# Emat.net
KiCad netlist of a schematic drawn in EAGLE
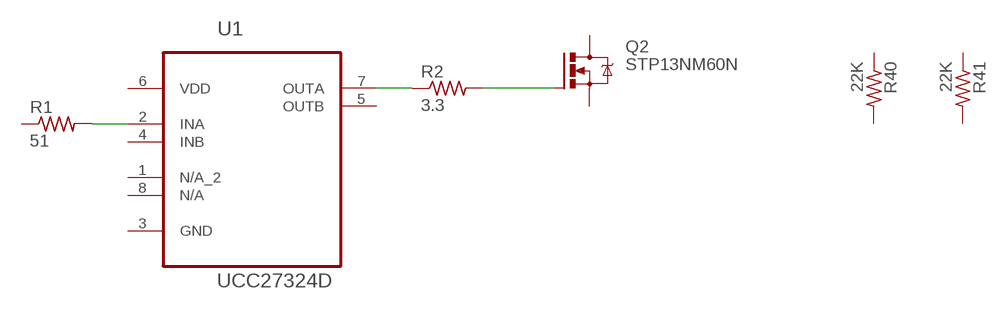
[diagram p0: schematic, sheet 1]

(export (version "E")
  (design (tool "Eeschema 10.0.6"))
  (components
    (comp (ref "Q2")
      (value "STP13NM60N")
      (footprint "eagle-import:TO220BV")
      (libsource (lib "eagle-import") (part "STP13NM60N"))
    )
    (comp (ref "R1")
      (value "51")
      (footprint "eagle-import:R1206")
      (libsource (lib "eagle-import") (part "R-US_R1206"))
    )
    (comp (ref "R2")
      (value "3.3")
      (footprint "eagle-import:R1206")
      (libsource (lib "eagle-import") (part "R-US_R1206"))
    )
    (comp (ref "R40")
      (value "22K")
      (footprint "eagle-import:R2512")
      (libsource (lib "eagle-import") (part "R-US_R2512"))
    )
    (comp (ref "R41")
      (value "22K")
      (footprint "eagle-import:R2512")
      (libsource (lib "eagle-import") (part "R-US_R2512"))
    )
    (comp (ref "U1")
      (value "UCC27324D")
      (footprint "eagle-import:SOIC127P600X175-8N")
      (libsource (lib "eagle-import") (part "UCC27324D"))
    )
  )
  (nets
    (net (code "1") (name "/VDD") (class "Default")
      (node (ref "U1") (pin "6") (pinfunction "VDD_6") (pintype "power_in"))
    )
    (net (code "2") (name "Net-(Q2-PadG)") (class "Default")
      (node (ref "Q2") (pin "G") (pinfunction "G_G") (pintype "passive"))
      (node (ref "R2") (pin "2") (pinfunction "2_2") (pintype "passive"))
    )
    (net (code "3") (name "Net-(U1-INA)") (class "Default")
      (node (ref "R1") (pin "2") (pinfunction "2_2") (pintype "passive"))
      (node (ref "U1") (pin "2") (pinfunction "INA_2") (pintype "input"))
    )
    (net (code "4") (name "Net-(U1-OUTA)") (class "Default")
      (node (ref "R2") (pin "1") (pinfunction "1_1") (pintype "passive"))
      (node (ref "U1") (pin "7") (pinfunction "OUTA_7") (pintype "output"))
    )
    (net (code "5") (name "unconnected-(Q2-PadD)") (class "Default")
      (node (ref "Q2") (pin "D") (pinfunction "D_D") (pintype "passive"))
    )
    (net (code "6") (name "unconnected-(Q2-PadS)") (class "Default")
      (node (ref "Q2") (pin "S") (pinfunction "S_S") (pintype "passive"))
    )
    (net (code "7") (name "unconnected-(R1-Pad1)") (class "Default")
      (node (ref "R1") (pin "1") (pinfunction "1_1") (pintype "passive"))
    )
    (net (code "8") (name "unconnected-(R40-Pad1)") (class "Default")
      (node (ref "R40") (pin "1") (pinfunction "1_1") (pintype "passive"))
    )
    (net (code "9") (name "unconnected-(R40-Pad2)") (class "Default")
      (node (ref "R40") (pin "2") (pinfunction "2_2") (pintype "passive"))
    )
    (net (code "10") (name "unconnected-(R41-Pad1)") (class "Default")
      (node (ref "R41") (pin "1") (pinfunction "1_1") (pintype "passive"))
    )
    (net (code "11") (name "unconnected-(R41-Pad2)") (class "Default")
      (node (ref "R41") (pin "2") (pinfunction "2_2") (pintype "passive"))
    )
    (net (code "12") (name "unconnected-(U1-GND-Pad3)") (class "Default")
      (node (ref "U1") (pin "3") (pinfunction "GND_3") (pintype "passive"))
    )
    (net (code "13") (name "unconnected-(U1-INB-Pad4)") (class "Default")
      (node (ref "U1") (pin "4") (pinfunction "INB_4") (pintype "input"))
    )
    (net (code "14") (name "unconnected-(U1-N{slash}A-Pad8)") (class "Default")
      (node (ref "U1") (pin "8") (pinfunction "N/A_8") (pintype "no_connect"))
    )
    (net (code "15") (name "unconnected-(U1-N{slash}A_2-Pad1)") (class "Default")
      (node (ref "U1") (pin "1") (pinfunction "N/A_2_1") (pintype "no_connect"))
    )
    (net (code "16") (name "unconnected-(U1-OUTB-Pad5)") (class "Default")
      (node (ref "U1") (pin "5") (pinfunction "OUTB_5") (pintype "output"))
    )
  )
)
